# ICS43432_pi_stereo_0_1.net
KiCad netlist of a schematic drawn in EAGLE
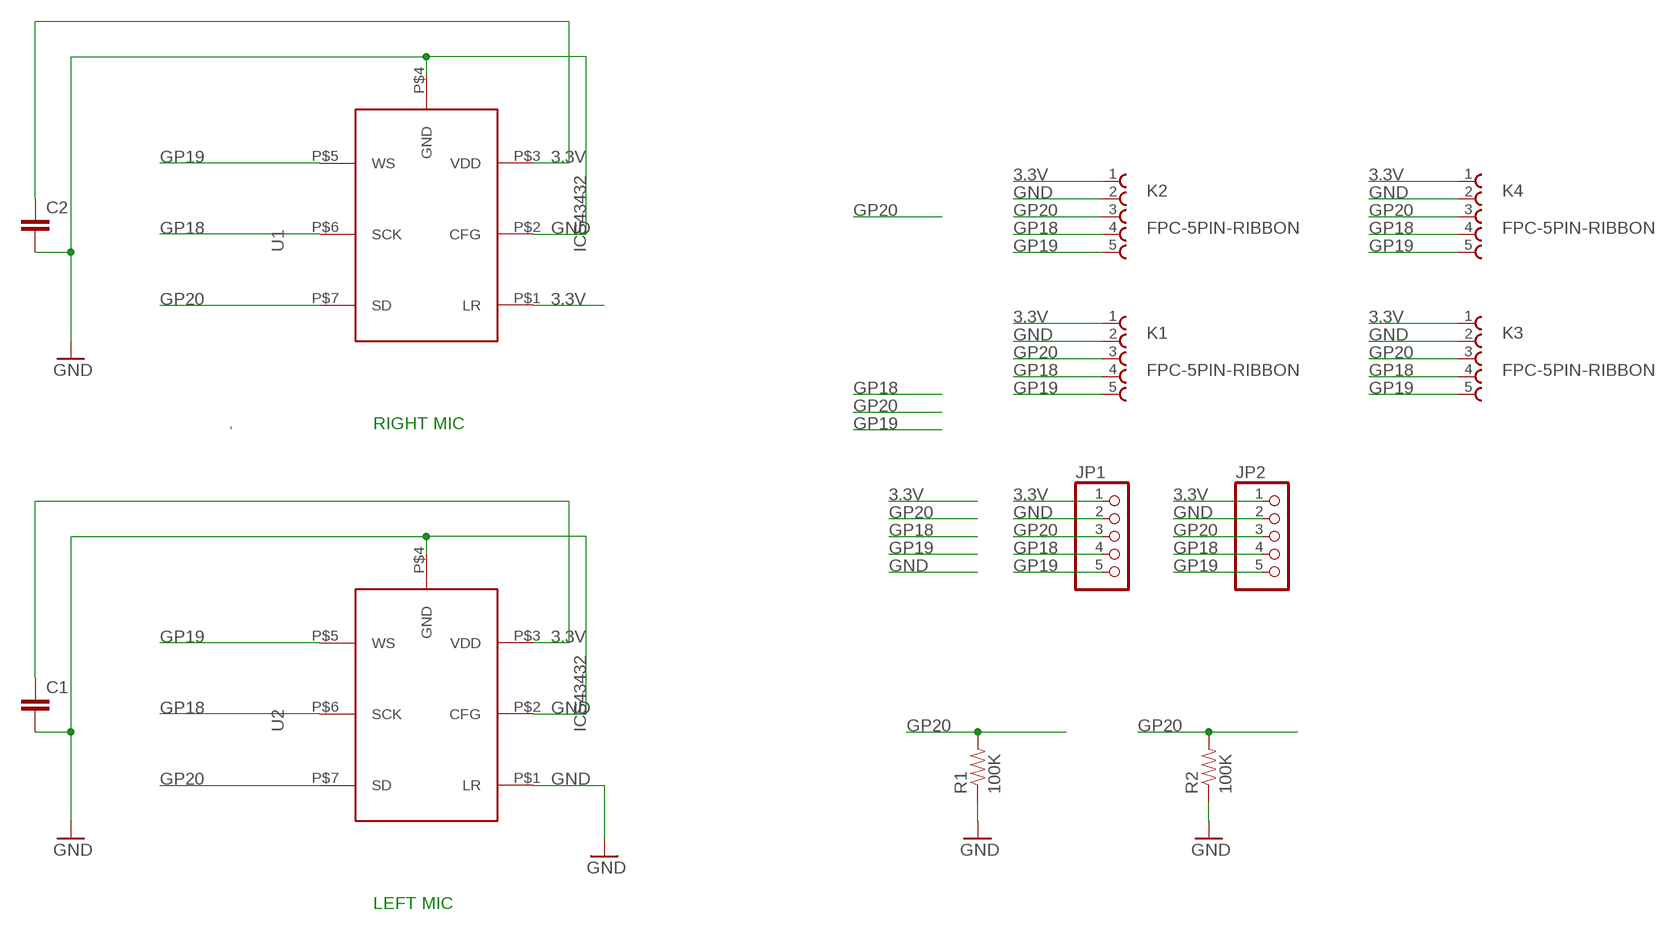
[diagram p0: schematic, sheet 1]

(export (version "E")
  (design (tool "Eeschema 10.0.6"))
  (components
    (comp (ref "C1")
      (value "CAP0402-CAP")
      (footprint "eagle-import:0402-CAP")
      (libsource (lib "eagle-import") (part "CAP0402-CAP"))
    )
    (comp (ref "C2")
      (value "CAP0402-CAP")
      (footprint "eagle-import:0402-CAP")
      (libsource (lib "eagle-import") (part "CAP0402-CAP"))
    )
    (comp (ref "JP1")
      (value "HEADER-1X5ROUND")
      (footprint "eagle-import:1X05_ROUND")
      (libsource (lib "eagle-import") (part "HEADER-1X5ROUND"))
    )
    (comp (ref "JP2")
      (value "HEADER-1X5ROUND")
      (footprint "eagle-import:1X05_ROUND")
      (libsource (lib "eagle-import") (part "HEADER-1X5ROUND"))
    )
    (comp (ref "K1")
      (value "FPC-5PIN-RIBBON")
      (footprint "eagle-import:5PIN_FPC")
      (libsource (lib "eagle-import") (part "FPC-5PIN-RIBBON"))
    )
    (comp (ref "K2")
      (value "FPC-5PIN-RIBBON")
      (footprint "eagle-import:5PIN_FPC")
      (libsource (lib "eagle-import") (part "FPC-5PIN-RIBBON"))
    )
    (comp (ref "K3")
      (value "FPC-5PIN-RIBBON")
      (footprint "eagle-import:5PIN_FPC")
      (libsource (lib "eagle-import") (part "FPC-5PIN-RIBBON"))
    )
    (comp (ref "K4")
      (value "FPC-5PIN-RIBBON")
      (footprint "eagle-import:5PIN_FPC")
      (libsource (lib "eagle-import") (part "FPC-5PIN-RIBBON"))
    )
    (comp (ref "R1")
      (value "100K")
      (footprint "eagle-import:0402-RES")
      (libsource (lib "eagle-import") (part "RESISTOR0402"))
    )
    (comp (ref "R2")
      (value "100K")
      (footprint "eagle-import:0402-RES")
      (libsource (lib "eagle-import") (part "RESISTOR0402"))
    )
    (comp (ref "U1")
      (value "ICS43432")
      (footprint "eagle-import:ICS43432")
      (libsource (lib "eagle-import") (part "ICS43432"))
    )
    (comp (ref "U2")
      (value "ICS43432")
      (footprint "eagle-import:ICS43432")
      (libsource (lib "eagle-import") (part "ICS43432"))
    )
  )
  (nets
    (net (code "1") (name "/3.3V") (class "Default")
      (node (ref "C1") (pin "1") (pinfunction "1_1") (pintype "passive"))
      (node (ref "C2") (pin "1") (pinfunction "1_1") (pintype "passive"))
      (node (ref "JP1") (pin "1") (pinfunction "1_1") (pintype "passive"))
      (node (ref "JP2") (pin "1") (pinfunction "1_1") (pintype "passive"))
      (node (ref "K1") (pin "1") (pinfunction "1_1") (pintype "passive"))
      (node (ref "K2") (pin "1") (pinfunction "1_1") (pintype "passive"))
      (node (ref "K3") (pin "1") (pinfunction "1_1") (pintype "passive"))
      (node (ref "K4") (pin "1") (pinfunction "1_1") (pintype "passive"))
      (node (ref "U1") (pin "P$1") (pinfunction "LR_P$1") (pintype "bidirectional"))
      (node (ref "U1") (pin "P$3") (pinfunction "VDD_P$3") (pintype "bidirectional"))
      (node (ref "U2") (pin "P$3") (pinfunction "VDD_P$3") (pintype "bidirectional"))
    )
    (net (code "2") (name "/GP18") (class "Default")
      (node (ref "JP1") (pin "4") (pinfunction "4_4") (pintype "passive"))
      (node (ref "JP2") (pin "4") (pinfunction "4_4") (pintype "passive"))
      (node (ref "K1") (pin "4") (pinfunction "4_4") (pintype "passive"))
      (node (ref "K2") (pin "4") (pinfunction "4_4") (pintype "passive"))
      (node (ref "K3") (pin "4") (pinfunction "4_4") (pintype "passive"))
      (node (ref "K4") (pin "4") (pinfunction "4_4") (pintype "passive"))
      (node (ref "U1") (pin "P$6") (pinfunction "SCK_P$6") (pintype "bidirectional"))
      (node (ref "U2") (pin "P$6") (pinfunction "SCK_P$6") (pintype "bidirectional"))
    )
    (net (code "3") (name "/GP19") (class "Default")
      (node (ref "JP1") (pin "5") (pinfunction "5_5") (pintype "passive"))
      (node (ref "JP2") (pin "5") (pinfunction "5_5") (pintype "passive"))
      (node (ref "K1") (pin "5") (pinfunction "5_5") (pintype "passive"))
      (node (ref "K2") (pin "5") (pinfunction "5_5") (pintype "passive"))
      (node (ref "K3") (pin "5") (pinfunction "5_5") (pintype "passive"))
      (node (ref "K4") (pin "5") (pinfunction "5_5") (pintype "passive"))
      (node (ref "U1") (pin "P$5") (pinfunction "WS_P$5") (pintype "bidirectional"))
      (node (ref "U2") (pin "P$5") (pinfunction "WS_P$5") (pintype "bidirectional"))
    )
    (net (code "4") (name "/GP20") (class "Default")
      (node (ref "JP1") (pin "3") (pinfunction "3_3") (pintype "passive"))
      (node (ref "JP2") (pin "3") (pinfunction "3_3") (pintype "passive"))
      (node (ref "K1") (pin "3") (pinfunction "3_3") (pintype "passive"))
      (node (ref "K2") (pin "3") (pinfunction "3_3") (pintype "passive"))
      (node (ref "K3") (pin "3") (pinfunction "3_3") (pintype "passive"))
      (node (ref "K4") (pin "3") (pinfunction "3_3") (pintype "passive"))
      (node (ref "R1") (pin "2") (pinfunction "2_2") (pintype "passive"))
      (node (ref "R2") (pin "2") (pinfunction "2_2") (pintype "passive"))
      (node (ref "U1") (pin "P$7") (pinfunction "SD_P$7") (pintype "bidirectional"))
      (node (ref "U2") (pin "P$7") (pinfunction "SD_P$7") (pintype "bidirectional"))
    )
    (net (code "5") (name "GND") (class "Default")
      (node (ref "C1") (pin "2") (pinfunction "2_2") (pintype "passive"))
      (node (ref "C2") (pin "2") (pinfunction "2_2") (pintype "passive"))
      (node (ref "JP1") (pin "2") (pinfunction "2_2") (pintype "passive"))
      (node (ref "JP2") (pin "2") (pinfunction "2_2") (pintype "passive"))
      (node (ref "K1") (pin "2") (pinfunction "2_2") (pintype "passive"))
      (node (ref "K2") (pin "2") (pinfunction "2_2") (pintype "passive"))
      (node (ref "K3") (pin "2") (pinfunction "2_2") (pintype "passive"))
      (node (ref "K4") (pin "2") (pinfunction "2_2") (pintype "passive"))
      (node (ref "R1") (pin "1") (pinfunction "1_1") (pintype "passive"))
      (node (ref "R2") (pin "1") (pinfunction "1_1") (pintype "passive"))
      (node (ref "U1") (pin "P$2") (pinfunction "CFG_P$2") (pintype "bidirectional"))
      (node (ref "U1") (pin "P$4") (pinfunction "GND_P$4") (pintype "bidirectional"))
      (node (ref "U2") (pin "P$1") (pinfunction "LR_P$1") (pintype "bidirectional"))
      (node (ref "U2") (pin "P$2") (pinfunction "CFG_P$2") (pintype "bidirectional"))
      (node (ref "U2") (pin "P$4") (pinfunction "GND_P$4") (pintype "bidirectional"))
    )
  )
)
